# Schematic.net
KiCad netlist of a schematic drawn in EAGLE
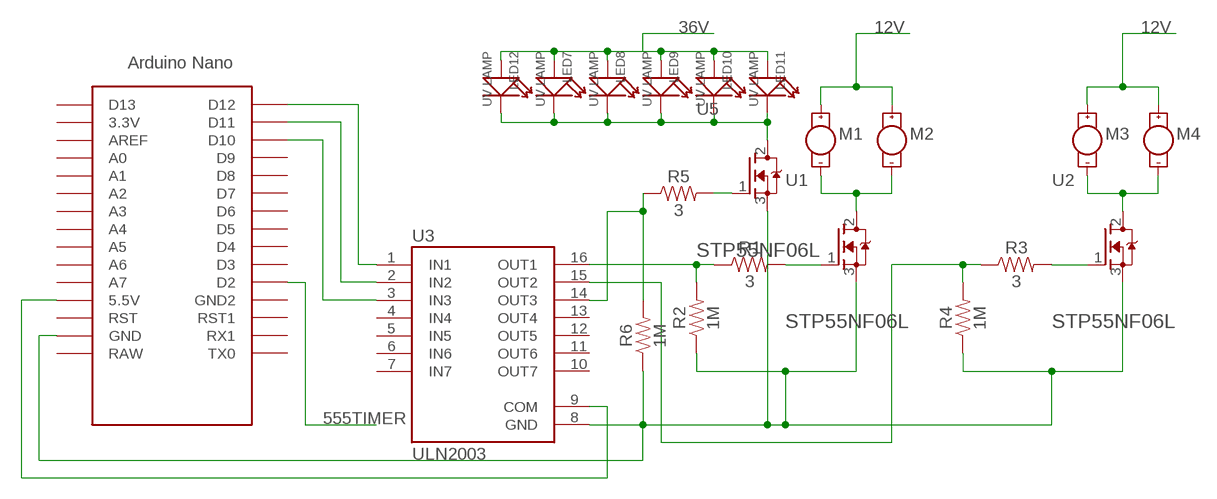
[diagram p0: schematic, sheet 1]

(export (version "E")
  (design (tool "Eeschema 10.0.6"))
  (components
    (comp (ref "LED7")
      (value "UV LAMP")
      (footprint "eagle-import:LED2-2.54-D10MM")
      (fields (field (name "MF") "Chengguangxing") (field (name "MP") "SR1004DC"))
      (libsource (lib "eagle-import") (part "DIP-LED-RED-RED-10MM(2P-D10MM)"))
    )
    (comp (ref "LED8")
      (value "UV LAMP")
      (footprint "eagle-import:LED2-2.54-D10MM")
      (fields (field (name "MF") "Chengguangxing") (field (name "MP") "SR1004DC"))
      (libsource (lib "eagle-import") (part "DIP-LED-RED-RED-10MM(2P-D10MM)"))
    )
    (comp (ref "LED9")
      (value "UV LAMP")
      (footprint "eagle-import:LED2-2.54-D10MM")
      (fields (field (name "MF") "Chengguangxing") (field (name "MP") "SR1004DC"))
      (libsource (lib "eagle-import") (part "DIP-LED-RED-RED-10MM(2P-D10MM)"))
    )
    (comp (ref "LED10")
      (value "UV LAMP")
      (footprint "eagle-import:LED2-2.54-D10MM")
      (fields (field (name "MF") "Chengguangxing") (field (name "MP") "SR1004DC"))
      (libsource (lib "eagle-import") (part "DIP-LED-RED-RED-10MM(2P-D10MM)"))
    )
    (comp (ref "LED11")
      (value "UV LAMP")
      (footprint "eagle-import:LED2-2.54-D10MM")
      (fields (field (name "MF") "Chengguangxing") (field (name "MP") "SR1004DC"))
      (libsource (lib "eagle-import") (part "DIP-LED-RED-RED-10MM(2P-D10MM)"))
    )
    (comp (ref "LED12")
      (value "UV LAMP")
      (footprint "eagle-import:LED2-2.54-D10MM")
      (fields (field (name "MF") "Chengguangxing") (field (name "MP") "SR1004DC"))
      (libsource (lib "eagle-import") (part "DIP-LED-RED-RED-10MM(2P-D10MM)"))
    )
    (comp (ref "M1")
      (value "MOTOR10MM")
      (footprint "eagle-import:VIBE-MOTOR-10MM")
      (libsource (lib "eagle-import") (part "MOTOR10MM"))
    )
    (comp (ref "M2")
      (value "MOTOR10MM")
      (footprint "eagle-import:VIBE-MOTOR-10MM")
      (libsource (lib "eagle-import") (part "MOTOR10MM"))
    )
    (comp (ref "M3")
      (value "MOTOR10MM")
      (footprint "eagle-import:VIBE-MOTOR-10MM")
      (libsource (lib "eagle-import") (part "MOTOR10MM"))
    )
    (comp (ref "M4")
      (value "MOTOR10MM")
      (footprint "eagle-import:VIBE-MOTOR-10MM")
      (libsource (lib "eagle-import") (part "MOTOR10MM"))
    )
    (comp (ref "R1")
      (value "3")
      (footprint "eagle-import:1210")
      (libsource (lib "eagle-import") (part "0.1OHM-1210-1/2W-1%"))
    )
    (comp (ref "R2")
      (value "1M")
      (footprint "eagle-import:1210")
      (libsource (lib "eagle-import") (part "0.1OHM-1210-1/2W-1%"))
    )
    (comp (ref "R3")
      (value "3")
      (footprint "eagle-import:1210")
      (libsource (lib "eagle-import") (part "0.1OHM-1210-1/2W-1%"))
    )
    (comp (ref "R4")
      (value "1M")
      (footprint "eagle-import:1210")
      (libsource (lib "eagle-import") (part "0.1OHM-1210-1/2W-1%"))
    )
    (comp (ref "R5")
      (value "3")
      (footprint "eagle-import:1210")
      (libsource (lib "eagle-import") (part "0.1OHM-1210-1/2W-1%"))
    )
    (comp (ref "R6")
      (value "1M")
      (footprint "eagle-import:1210")
      (libsource (lib "eagle-import") (part "0.1OHM-1210-1/2W-1%"))
    )
    (comp (ref "U$1")
      (value "NANO")
      (footprint "eagle-import:NANO")
      (libsource (lib "eagle-import") (part "NANO"))
    )
    (comp (ref "U1")
      (value "STP55NF06L")
      (footprint "eagle-import:TO254P1040X460X1935-3")
      (fields (field (name "MF") "STMicroelectronics"))
      (libsource (lib "eagle-import") (part "STP55NF06L"))
    )
    (comp (ref "U2")
      (value "STP55NF06L")
      (footprint "eagle-import:TO254P1040X460X1935-3")
      (fields (field (name "MF") "STMicroelectronics"))
      (libsource (lib "eagle-import") (part "STP55NF06L"))
    )
    (comp (ref "U3")
      (value "ULN2003")
      (footprint "eagle-import:DIP762W46P254L1969H533Q16")
      (fields (field (name "MF") "ON Semiconductor"))
      (libsource (lib "eagle-import") (part "ULN2003"))
    )
    (comp (ref "U5")
      (value "STP55NF06L")
      (footprint "eagle-import:TO254P1040X460X1935-3")
      (fields (field (name "MF") "STMicroelectronics"))
      (libsource (lib "eagle-import") (part "STP55NF06L"))
    )
  )
  (nets
    (net (code "1") (name "/12V") (class "Default")
      (node (ref "M1") (pin "+") (pinfunction "+_+") (pintype "bidirectional"))
      (node (ref "M2") (pin "+") (pinfunction "+_+") (pintype "bidirectional"))
      (node (ref "M3") (pin "+") (pinfunction "+_+") (pintype "bidirectional"))
      (node (ref "M4") (pin "+") (pinfunction "+_+") (pintype "bidirectional"))
    )
    (net (code "2") (name "/36V") (class "Default")
      (node (ref "LED10") (pin "+") (pinfunction "+_+") (pintype "passive"))
      (node (ref "LED11") (pin "+") (pinfunction "+_+") (pintype "passive"))
      (node (ref "LED12") (pin "+") (pinfunction "+_+") (pintype "passive"))
      (node (ref "LED7") (pin "+") (pinfunction "+_+") (pintype "passive"))
      (node (ref "LED8") (pin "+") (pinfunction "+_+") (pintype "passive"))
      (node (ref "LED9") (pin "+") (pinfunction "+_+") (pintype "passive"))
    )
    (net (code "3") (name "/555TIMER") (class "Default")
      (node (ref "U$1") (pin "D2") (pinfunction "D2_D2") (pintype "bidirectional"))
    )
    (net (code "4") (name "Net-(U$1-5.5V)") (class "Default")
      (node (ref "U$1") (pin "5V") (pinfunction "5.5V_5V") (pintype "bidirectional"))
      (node (ref "U3") (pin "9") (pinfunction "COM_9") (pintype "power_in"))
    )
    (net (code "5") (name "Net-(U1-D)") (class "Default")
      (node (ref "M1") (pin "-") (pinfunction "-_-") (pintype "bidirectional"))
      (node (ref "M2") (pin "-") (pinfunction "-_-") (pintype "bidirectional"))
      (node (ref "U1") (pin "2") (pinfunction "D_2") (pintype "passive"))
    )
    (net (code "6") (name "Net-(U1-G)") (class "Default")
      (node (ref "R1") (pin "2") (pinfunction "2_2") (pintype "passive"))
      (node (ref "U1") (pin "1") (pinfunction "G_1") (pintype "passive"))
    )
    (net (code "7") (name "Net-(U1-S)") (class "Default")
      (node (ref "R2") (pin "1") (pinfunction "1_1") (pintype "passive"))
      (node (ref "R4") (pin "1") (pinfunction "1_1") (pintype "passive"))
      (node (ref "R6") (pin "1") (pinfunction "1_1") (pintype "passive"))
      (node (ref "U$1") (pin "GND") (pinfunction "GND_GND") (pintype "bidirectional"))
      (node (ref "U1") (pin "3") (pinfunction "S_3") (pintype "passive"))
      (node (ref "U2") (pin "3") (pinfunction "S_3") (pintype "passive"))
      (node (ref "U3") (pin "8") (pinfunction "GND_8") (pintype "power_in"))
      (node (ref "U5") (pin "3") (pinfunction "S_3") (pintype "passive"))
    )
    (net (code "8") (name "Net-(U2-D)") (class "Default")
      (node (ref "M3") (pin "-") (pinfunction "-_-") (pintype "bidirectional"))
      (node (ref "M4") (pin "-") (pinfunction "-_-") (pintype "bidirectional"))
      (node (ref "U2") (pin "2") (pinfunction "D_2") (pintype "passive"))
    )
    (net (code "9") (name "Net-(U2-G)") (class "Default")
      (node (ref "R3") (pin "2") (pinfunction "2_2") (pintype "passive"))
      (node (ref "U2") (pin "1") (pinfunction "G_1") (pintype "passive"))
    )
    (net (code "10") (name "Net-(U3-IN1)") (class "Default")
      (node (ref "U$1") (pin "D12") (pinfunction "D12_D12") (pintype "bidirectional"))
      (node (ref "U3") (pin "1") (pinfunction "IN1_1") (pintype "input"))
    )
    (net (code "11") (name "Net-(U3-IN2)") (class "Default")
      (node (ref "U$1") (pin "D11") (pinfunction "D11_D11") (pintype "bidirectional"))
      (node (ref "U3") (pin "2") (pinfunction "IN2_2") (pintype "input"))
    )
    (net (code "12") (name "Net-(U3-IN3)") (class "Default")
      (node (ref "U$1") (pin "D10") (pinfunction "D10_D10") (pintype "bidirectional"))
      (node (ref "U3") (pin "3") (pinfunction "IN3_3") (pintype "input"))
    )
    (net (code "13") (name "Net-(U3-OUT1)") (class "Default")
      (node (ref "R1") (pin "1") (pinfunction "1_1") (pintype "passive"))
      (node (ref "R2") (pin "2") (pinfunction "2_2") (pintype "passive"))
      (node (ref "U3") (pin "16") (pinfunction "OUT1_16") (pintype "output"))
    )
    (net (code "14") (name "Net-(U3-OUT2)") (class "Default")
      (node (ref "R3") (pin "1") (pinfunction "1_1") (pintype "passive"))
      (node (ref "R4") (pin "2") (pinfunction "2_2") (pintype "passive"))
      (node (ref "U3") (pin "15") (pinfunction "OUT2_15") (pintype "output"))
    )
    (net (code "15") (name "Net-(U3-OUT3)") (class "Default")
      (node (ref "R5") (pin "1") (pinfunction "1_1") (pintype "passive"))
      (node (ref "R6") (pin "2") (pinfunction "2_2") (pintype "passive"))
      (node (ref "U3") (pin "14") (pinfunction "OUT3_14") (pintype "output"))
    )
    (net (code "16") (name "Net-(U5-D)") (class "Default")
      (node (ref "LED10") (pin "-") (pinfunction "-_-") (pintype "passive"))
      (node (ref "LED11") (pin "-") (pinfunction "-_-") (pintype "passive"))
      (node (ref "LED12") (pin "-") (pinfunction "-_-") (pintype "passive"))
      (node (ref "LED7") (pin "-") (pinfunction "-_-") (pintype "passive"))
      (node (ref "LED8") (pin "-") (pinfunction "-_-") (pintype "passive"))
      (node (ref "LED9") (pin "-") (pinfunction "-_-") (pintype "passive"))
      (node (ref "U5") (pin "2") (pinfunction "D_2") (pintype "passive"))
    )
    (net (code "17") (name "Net-(U5-G)") (class "Default")
      (node (ref "R5") (pin "2") (pinfunction "2_2") (pintype "passive"))
      (node (ref "U5") (pin "1") (pinfunction "G_1") (pintype "passive"))
    )
    (net (code "18") (name "unconnected-(U$1-GND2-PadGND1)") (class "Default")
      (node (ref "U$1") (pin "GND1") (pinfunction "GND2_GND1") (pintype "bidirectional"))
    )
    (net (code "19") (name "unconnected-(U$1-Pad3.3V)") (class "Default")
      (node (ref "U$1") (pin "3.3V") (pinfunction "3.3V_3.3V") (pintype "bidirectional"))
    )
    (net (code "20") (name "unconnected-(U$1-PadA0)") (class "Default")
      (node (ref "U$1") (pin "A0") (pinfunction "A0_A0") (pintype "bidirectional"))
    )
    (net (code "21") (name "unconnected-(U$1-PadA1)") (class "Default")
      (node (ref "U$1") (pin "A1") (pinfunction "A1_A1") (pintype "bidirectional"))
    )
    (net (code "22") (name "unconnected-(U$1-PadA2)") (class "Default")
      (node (ref "U$1") (pin "A2") (pinfunction "A2_A2") (pintype "bidirectional"))
    )
    (net (code "23") (name "unconnected-(U$1-PadA3)") (class "Default")
      (node (ref "U$1") (pin "A3") (pinfunction "A3_A3") (pintype "bidirectional"))
    )
    (net (code "24") (name "unconnected-(U$1-PadA4)") (class "Default")
      (node (ref "U$1") (pin "A4") (pinfunction "A4_A4") (pintype "bidirectional"))
    )
    (net (code "25") (name "unconnected-(U$1-PadA5)") (class "Default")
      (node (ref "U$1") (pin "A5") (pinfunction "A5_A5") (pintype "bidirectional"))
    )
    (net (code "26") (name "unconnected-(U$1-PadA6)") (class "Default")
      (node (ref "U$1") (pin "A6") (pinfunction "A6_A6") (pintype "bidirectional"))
    )
    (net (code "27") (name "unconnected-(U$1-PadA7)") (class "Default")
      (node (ref "U$1") (pin "A7") (pinfunction "A7_A7") (pintype "bidirectional"))
    )
    (net (code "28") (name "unconnected-(U$1-PadAREF)") (class "Default")
      (node (ref "U$1") (pin "AREF") (pinfunction "AREF_AREF") (pintype "bidirectional"))
    )
    (net (code "29") (name "unconnected-(U$1-PadD3)") (class "Default")
      (node (ref "U$1") (pin "D3") (pinfunction "D3_D3") (pintype "bidirectional"))
    )
    (net (code "30") (name "unconnected-(U$1-PadD4)") (class "Default")
      (node (ref "U$1") (pin "D4") (pinfunction "D4_D4") (pintype "bidirectional"))
    )
    (net (code "31") (name "unconnected-(U$1-PadD5)") (class "Default")
      (node (ref "U$1") (pin "D5") (pinfunction "D5_D5") (pintype "bidirectional"))
    )
    (net (code "32") (name "unconnected-(U$1-PadD6)") (class "Default")
      (node (ref "U$1") (pin "D6") (pinfunction "D6_D6") (pintype "bidirectional"))
    )
    (net (code "33") (name "unconnected-(U$1-PadD7)") (class "Default")
      (node (ref "U$1") (pin "D7") (pinfunction "D7_D7") (pintype "bidirectional"))
    )
    (net (code "34") (name "unconnected-(U$1-PadD8)") (class "Default")
      (node (ref "U$1") (pin "D8") (pinfunction "D8_D8") (pintype "bidirectional"))
    )
    (net (code "35") (name "unconnected-(U$1-PadD9)") (class "Default")
      (node (ref "U$1") (pin "D9") (pinfunction "D9_D9") (pintype "bidirectional"))
    )
    (net (code "36") (name "unconnected-(U$1-PadD13)") (class "Default")
      (node (ref "U$1") (pin "D13") (pinfunction "D13_D13") (pintype "bidirectional"))
    )
    (net (code "37") (name "unconnected-(U$1-PadICSP1)") (class "Default")
      (node (ref "U$1") (pin "ICSP1") (pinfunction "ICSP1_ICSP1") (pintype "bidirectional"))
    )
    (net (code "38") (name "unconnected-(U$1-PadICSP2)") (class "Default")
      (node (ref "U$1") (pin "ICSP2") (pinfunction "ICSP2_ICSP2") (pintype "bidirectional"))
    )
    (net (code "39") (name "unconnected-(U$1-PadICSP3)") (class "Default")
      (node (ref "U$1") (pin "ICSP3") (pinfunction "ICSP3_ICSP3") (pintype "bidirectional"))
    )
    (net (code "40") (name "unconnected-(U$1-PadICSP4)") (class "Default")
      (node (ref "U$1") (pin "ICSP4") (pinfunction "ICSP4_ICSP4") (pintype "bidirectional"))
    )
    (net (code "41") (name "unconnected-(U$1-PadICSP5)") (class "Default")
      (node (ref "U$1") (pin "ICSP5") (pinfunction "ICSP5_ICSP5") (pintype "bidirectional"))
    )
    (net (code "42") (name "unconnected-(U$1-PadICSP6)") (class "Default")
      (node (ref "U$1") (pin "ICSP6") (pinfunction "ICSP6_ICSP6") (pintype "bidirectional"))
    )
    (net (code "43") (name "unconnected-(U$1-PadRAW)") (class "Default")
      (node (ref "U$1") (pin "RAW") (pinfunction "RAW_RAW") (pintype "bidirectional"))
    )
    (net (code "44") (name "unconnected-(U$1-PadRST)") (class "Default")
      (node (ref "U$1") (pin "RST") (pinfunction "RST_RST") (pintype "bidirectional"))
    )
    (net (code "45") (name "unconnected-(U$1-PadRST1)") (class "Default")
      (node (ref "U$1") (pin "RST1") (pinfunction "RST1_RST1") (pintype "bidirectional"))
    )
    (net (code "46") (name "unconnected-(U$1-PadRX1)") (class "Default")
      (node (ref "U$1") (pin "RX1") (pinfunction "RX1_RX1") (pintype "bidirectional"))
    )
    (net (code "47") (name "unconnected-(U$1-PadTX0)") (class "Default")
      (node (ref "U$1") (pin "TX0") (pinfunction "TX0_TX0") (pintype "bidirectional"))
    )
    (net (code "48") (name "unconnected-(U3-IN4-Pad4)") (class "Default")
      (node (ref "U3") (pin "4") (pinfunction "IN4_4") (pintype "input"))
    )
    (net (code "49") (name "unconnected-(U3-IN5-Pad5)") (class "Default")
      (node (ref "U3") (pin "5") (pinfunction "IN5_5") (pintype "input"))
    )
    (net (code "50") (name "unconnected-(U3-IN6-Pad6)") (class "Default")
      (node (ref "U3") (pin "6") (pinfunction "IN6_6") (pintype "input"))
    )
    (net (code "51") (name "unconnected-(U3-IN7-Pad7)") (class "Default")
      (node (ref "U3") (pin "7") (pinfunction "IN7_7") (pintype "input"))
    )
    (net (code "52") (name "unconnected-(U3-OUT4-Pad13)") (class "Default")
      (node (ref "U3") (pin "13") (pinfunction "OUT4_13") (pintype "output"))
    )
    (net (code "53") (name "unconnected-(U3-OUT5-Pad12)") (class "Default")
      (node (ref "U3") (pin "12") (pinfunction "OUT5_12") (pintype "output"))
    )
    (net (code "54") (name "unconnected-(U3-OUT6-Pad11)") (class "Default")
      (node (ref "U3") (pin "11") (pinfunction "OUT6_11") (pintype "output"))
    )
    (net (code "55") (name "unconnected-(U3-OUT7-Pad10)") (class "Default")
      (node (ref "U3") (pin "10") (pinfunction "OUT7_10") (pintype "output"))
    )
  )
)
